# Speaker.net
KiCad netlist of a schematic drawn in Altium Designer
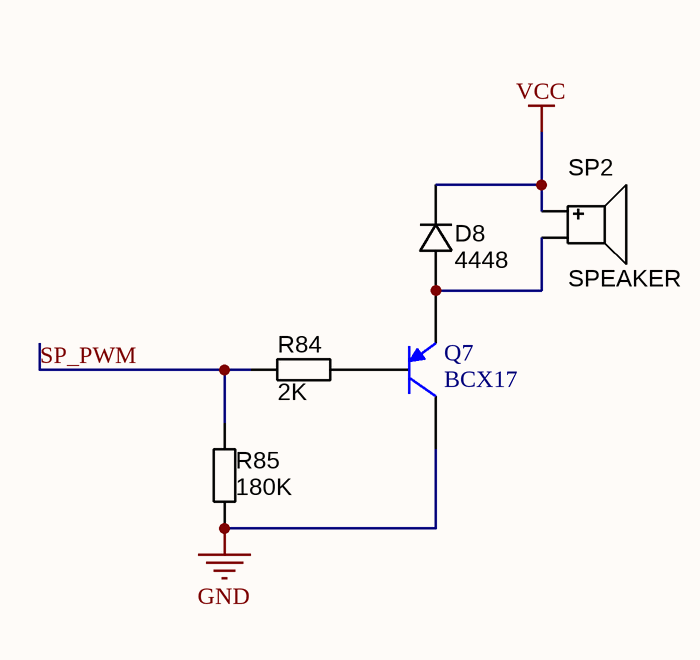
[diagram p0: Speaker.SchDoc]

(export (version "E")
  (design (tool "Eeschema 10.0.6"))
  (components
    (comp (ref "D8")
      (value "4448")
      (footprint "SOD523F")
      (description "Diode SMD small signal 0.2A SOD-523F")
      (libsource (lib "All_Library1") (part "DIODE_1N4148_200mA_SOD523F"))
    )
    (comp (ref "Q7")
      (value "BCX17")
      (footprint "SOT23-3N")
      (description "PNP General Purpose Transistors")
      (fields (field (name "PUBLISHER") "Altium Limited"))
      (libsource (lib "All_Library1") (part "BCX17"))
    )
    (comp (ref "R84")
      (value "2K")
      (footprint "RESC1005L")
      (description "Resistor SMD chip")
      (fields (field (name "TOLERANCE") "?%"))
      (libsource (lib "All_Library1") (part "RES_10K_0805_5%"))
    )
    (comp (ref "R85")
      (value "180K")
      (footprint "RESC1005L")
      (description "Resistor SMD chip")
      (fields (field (name "TOLERANCE") "?%"))
      (libsource (lib "PBL - Resistors") (part "RES_330R_0402_5%"))
    )
    (comp (ref "SP2")
      (value "Alternate part: 3100-932")
      (footprint "BUZZER_12.0X8.5MM")
      (description "Speaker, Magnetic Transducer")
      (fields (field (name "MANUFACTURER PART NUMBER 1") "SPEAKER"))
      (libsource (lib "PBL - Electromechanical") (part "BZ_12x8.5x6.5_2kHz"))
    )
  )
  (nets
    (net (code "1") (name "/SP_PWM") (class "Default")
      (node (ref "R84") (pin "1") (pinfunction "1_1") (pintype "passive"))
      (node (ref "R85") (pin "2") (pinfunction "2_2") (pintype "passive"))
    )
    (net (code "2") (name "GND") (class "Default")
      (node (ref "Q7") (pin "3") (pinfunction "C_3") (pintype "passive"))
      (node (ref "R85") (pin "1") (pinfunction "1_1") (pintype "passive"))
    )
    (net (code "3") (name "Net-(Q7-B)") (class "Default")
      (node (ref "Q7") (pin "1") (pinfunction "B_1") (pintype "passive"))
      (node (ref "R84") (pin "2") (pinfunction "2_2") (pintype "passive"))
    )
    (net (code "4") (name "Net-(Q7-E)") (class "Default")
      (node (ref "D8") (pin "A") (pinfunction "A_A") (pintype "passive"))
      (node (ref "Q7") (pin "2") (pinfunction "E_2") (pintype "passive"))
      (node (ref "SP2") (pin "2") (pinfunction "Negative_2") (pintype "passive"))
    )
    (net (code "5") (name "VCC") (class "Default")
      (node (ref "D8") (pin "K") (pinfunction "K_K") (pintype "passive"))
      (node (ref "SP2") (pin "1") (pinfunction "Positive_1") (pintype "passive"))
    )
  )
)
